# SCH_ECE198-03.net
KiCad netlist of a schematic drawn in EasyEDA
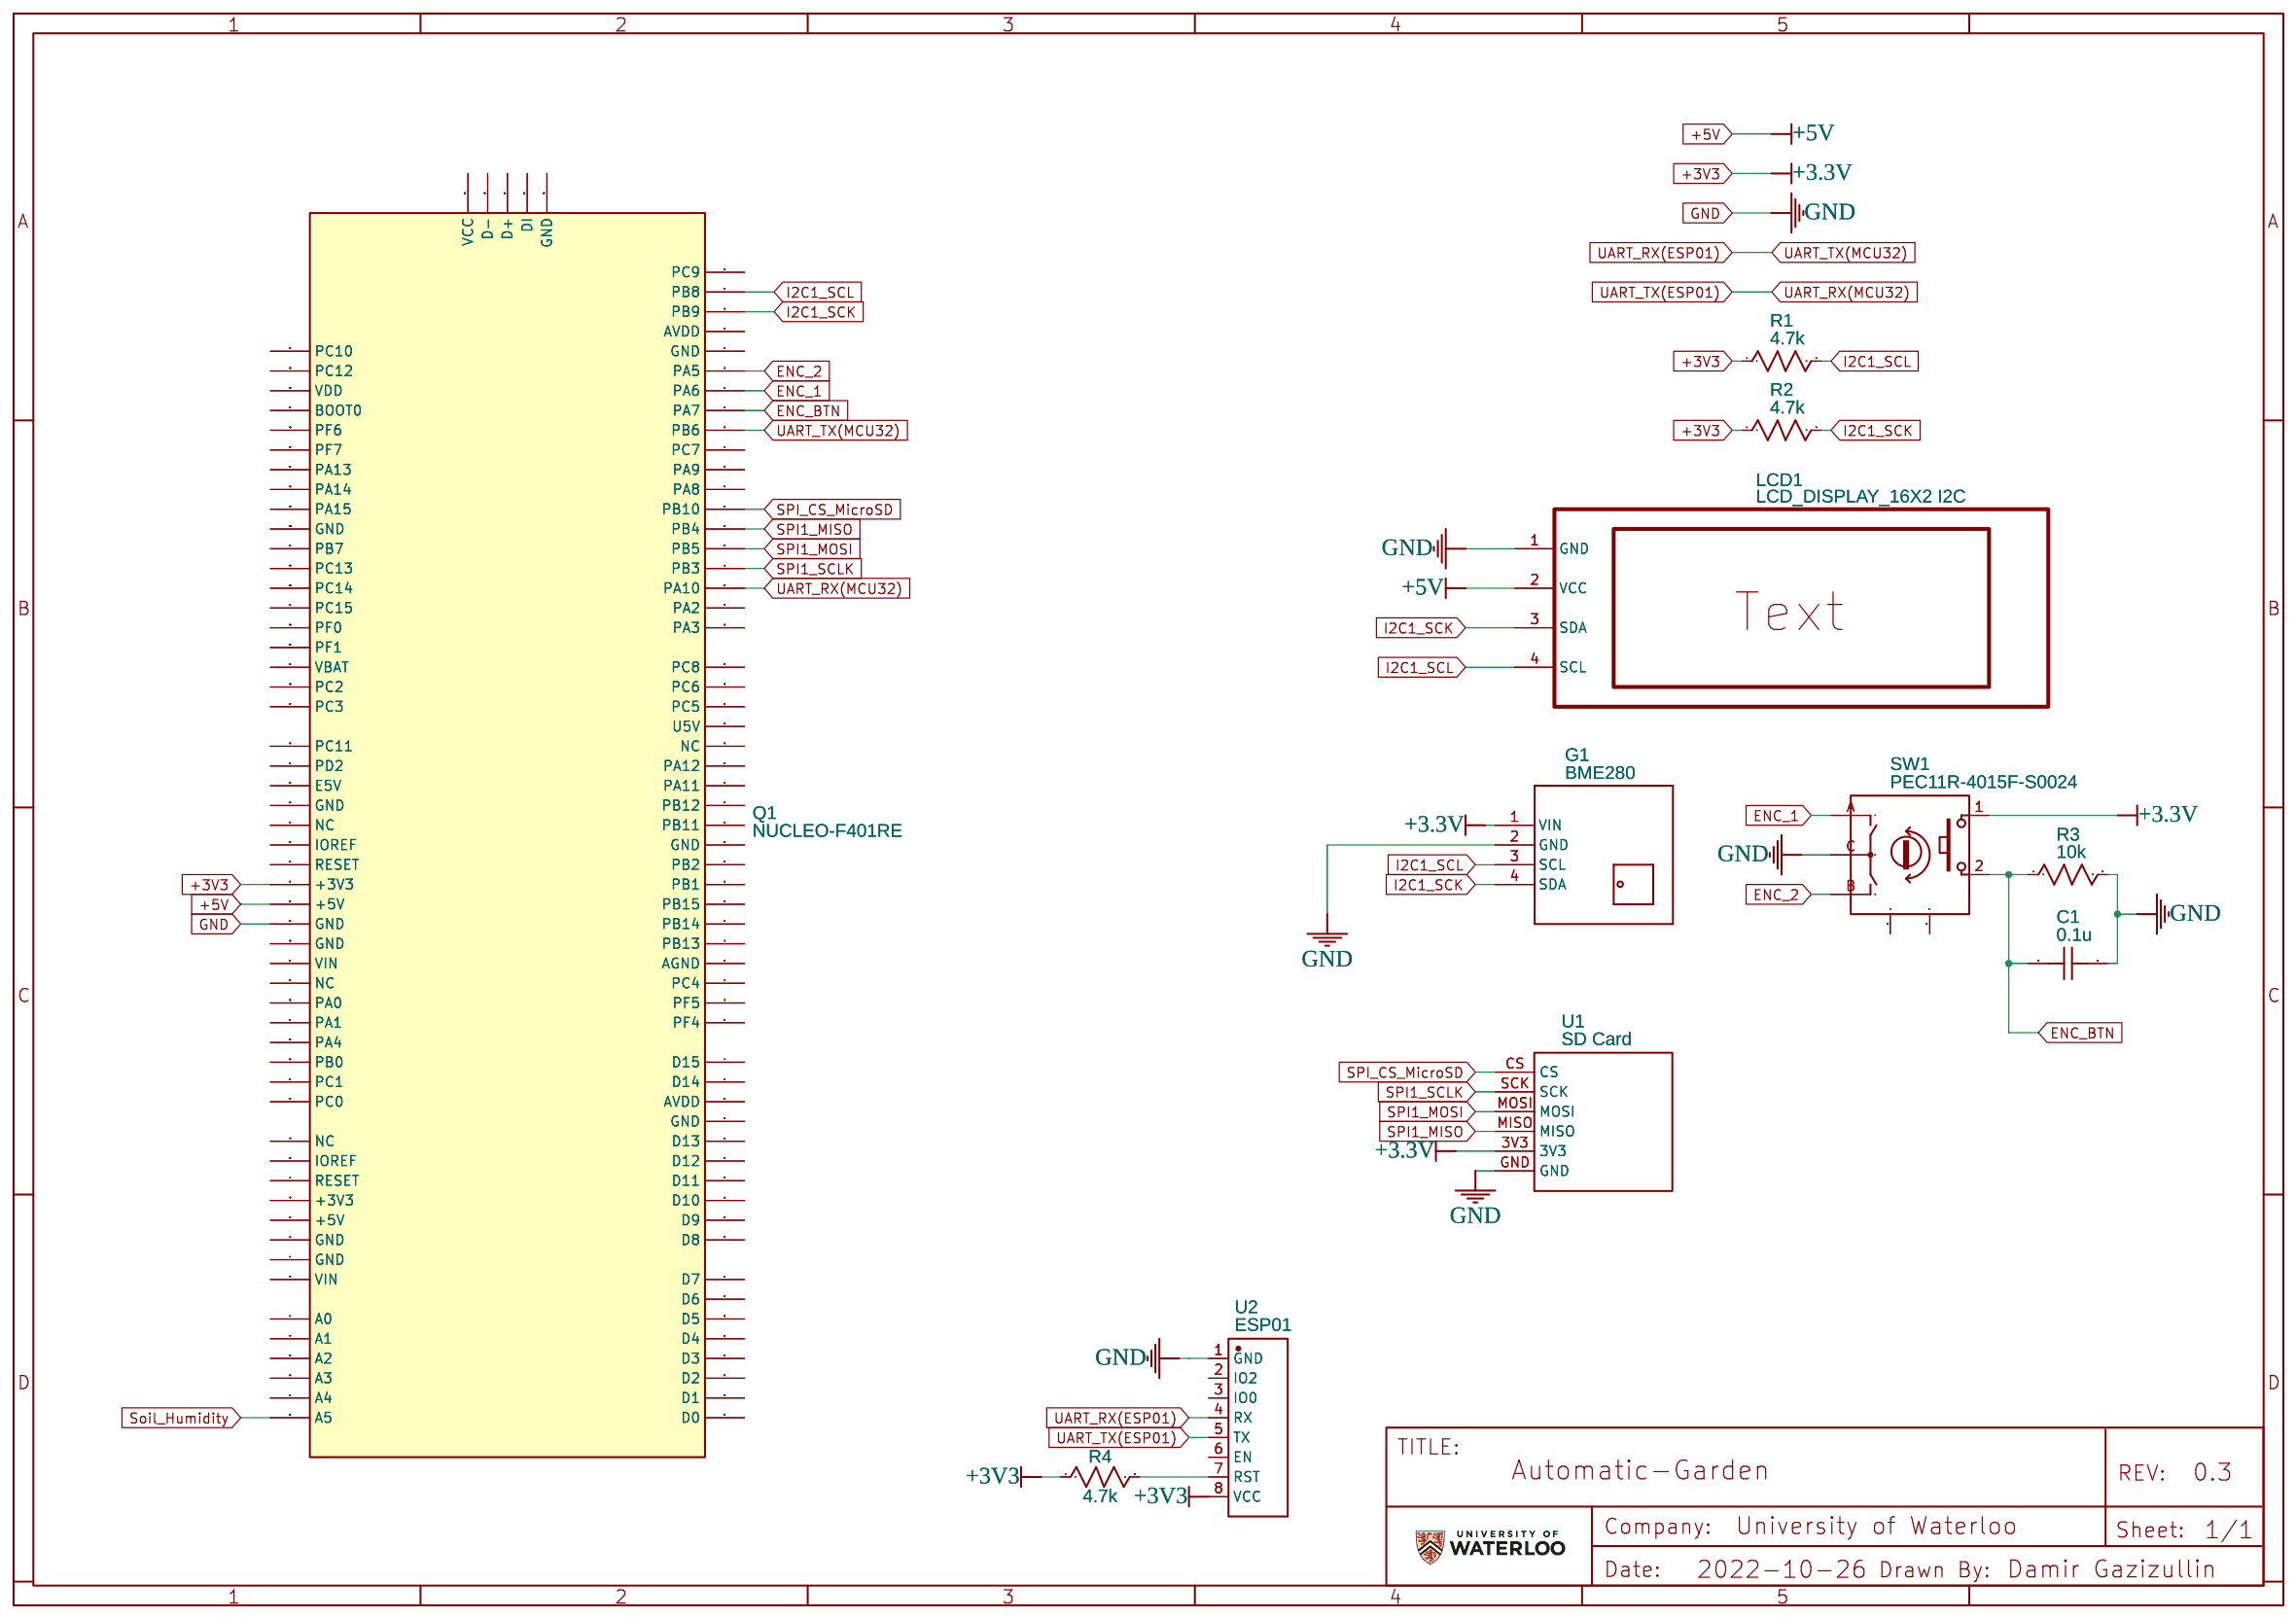
[diagram p0: schematic sheet]

(export (version "E")
  (design (tool "Eeschema 10.0.6"))
  (components
    (comp (ref "C1") (value "0.1u") (libsource (lib "") (part "C_0603_US")))
    (comp (ref "G1") (value "BME280") (libsource (lib "") (part "TEMP-HUM-PRES-BME280")))
    (comp (ref "LCD1") (value "LCD_DISPLAY_16X2 I2C") (libsource (lib "") (part "LCD_DISPLAY_16X2 I2C")))
    (comp (ref "Q1") (value "NUCLEO-F401RE") (libsource (lib "") (part "NUCLEO-F401RE")))
    (comp (ref "R1") (value "4.7k") (libsource (lib "") (part "R_0603_US")))
    (comp (ref "R2") (value "4.7k") (libsource (lib "") (part "R_0603_US")))
    (comp (ref "R3") (value "10k") (libsource (lib "") (part "R_AXIAL-0.5_US")))
    (comp (ref "R4") (value "4.7k") (libsource (lib "") (part "R_AXIAL-0.5_US")))
    (comp (ref "SW1")
      (value "PEC11R-4015F-S0024")
      (fields (field (name "BOM_Supplier Part") "C143789"))
      (libsource (lib "") (part "PEC11R-4015F-S0024"))
    )
    (comp (ref "U1") (value "SD Card") (libsource (lib "") (part "SD Card")))
    (comp (ref "U2") (value "ESP01") (libsource (lib "") (part "ESP01")))
  )
  (nets
    (net (code "1") (name "+3V3") (class "Default")
      (node (ref "G1") (pin "1") (pinfunction "VIN_1") (pintype "bidirectional"))
      (node (ref "Q1") (pin "91") (pinfunction "+3V3_91") (pintype "unspecified"))
      (node (ref "R1") (pin "1") (pinfunction "1_1") (pintype "unspecified"))
      (node (ref "R2") (pin "1") (pinfunction "1_1") (pintype "unspecified"))
      (node (ref "R4") (pin "1") (pinfunction "1_1") (pintype "unspecified"))
      (node (ref "SW1") (pin "1") (pinfunction "1_1") (pintype "unspecified"))
      (node (ref "U1") (pin "3V3") (pinfunction "3V3_3V3") (pintype "unspecified"))
      (node (ref "U2") (pin "8") (pinfunction "VCC_8") (pintype "unspecified"))
    )
    (net (code "2") (name "+5V") (class "Default")
      (node (ref "LCD1") (pin "2") (pinfunction "VCC_2") (pintype "passive"))
      (node (ref "Q1") (pin "90") (pinfunction "+5V_90") (pintype "unspecified"))
    )
    (net (code "3") (name "ENC_1") (class "Default")
      (node (ref "Q1") (pin "14") (pinfunction "PA6_14") (pintype "bidirectional"))
      (node (ref "SW1") (pin "A") (pinfunction "A_A") (pintype "unspecified"))
    )
    (net (code "4") (name "ENC_2") (class "Default")
      (node (ref "Q1") (pin "13") (pinfunction "PA5_13") (pintype "bidirectional"))
      (node (ref "SW1") (pin "B") (pinfunction "B_B") (pintype "unspecified"))
    )
    (net (code "5") (name "ENC_BTN") (class "Default")
      (node (ref "C1") (pin "1") (pinfunction "1_1") (pintype "unspecified"))
      (node (ref "Q1") (pin "15") (pinfunction "PA7_15") (pintype "bidirectional"))
      (node (ref "R3") (pin "1") (pinfunction "1_1") (pintype "unspecified"))
      (node (ref "SW1") (pin "2") (pinfunction "2_2") (pintype "unspecified"))
    )
    (net (code "6") (name "GND") (class "Default")
      (node (ref "C1") (pin "2") (pinfunction "2_2") (pintype "unspecified"))
      (node (ref "G1") (pin "2") (pinfunction "GND_2") (pintype "bidirectional"))
      (node (ref "LCD1") (pin "1") (pinfunction "GND_1") (pintype "passive"))
      (node (ref "Q1") (pin "89") (pinfunction "GND_89") (pintype "unspecified"))
      (node (ref "R3") (pin "2") (pinfunction "2_2") (pintype "unspecified"))
      (node (ref "SW1") (pin "C") (pinfunction "C_C") (pintype "unspecified"))
      (node (ref "U1") (pin "GND") (pinfunction "GND_GND") (pintype "unspecified"))
      (node (ref "U2") (pin "1") (pinfunction "GND_1") (pintype "unspecified"))
    )
    (net (code "7") (name "I2C1_SCK") (class "Default")
      (node (ref "G1") (pin "4") (pinfunction "SDA_4") (pintype "bidirectional"))
      (node (ref "LCD1") (pin "3") (pinfunction "SDA_3") (pintype "passive"))
      (node (ref "Q1") (pin "10") (pinfunction "PB9_10") (pintype "bidirectional"))
      (node (ref "R2") (pin "2") (pinfunction "2_2") (pintype "unspecified"))
    )
    (net (code "8") (name "I2C1_SCL") (class "Default")
      (node (ref "G1") (pin "3") (pinfunction "SCL_3") (pintype "bidirectional"))
      (node (ref "LCD1") (pin "4") (pinfunction "SCL_4") (pintype "passive"))
      (node (ref "Q1") (pin "9") (pinfunction "PB8_9") (pintype "bidirectional"))
      (node (ref "R1") (pin "2") (pinfunction "2_2") (pintype "unspecified"))
    )
    (net (code "9") (name "Net-(U2-RST)") (class "Default")
      (node (ref "R4") (pin "2") (pinfunction "2_2") (pintype "unspecified"))
      (node (ref "U2") (pin "7") (pinfunction "RST_7") (pintype "unspecified"))
    )
    (net (code "10") (name "SPI1_MISO") (class "Default")
      (node (ref "Q1") (pin "21") (pinfunction "PB4_21") (pintype "bidirectional"))
      (node (ref "U1") (pin "MISO") (pinfunction "MISO_MISO") (pintype "unspecified"))
    )
    (net (code "11") (name "SPI1_MOSI") (class "Default")
      (node (ref "Q1") (pin "22") (pinfunction "PB5_22") (pintype "bidirectional"))
      (node (ref "U1") (pin "MOSI") (pinfunction "MOSI_MOSI") (pintype "unspecified"))
    )
    (net (code "12") (name "SPI1_SCLK") (class "Default")
      (node (ref "Q1") (pin "23") (pinfunction "PB3_23") (pintype "bidirectional"))
      (node (ref "U1") (pin "SCK") (pinfunction "SCK_SCK") (pintype "unspecified"))
    )
    (net (code "13") (name "SPI_CS_MicroSD") (class "Default")
      (node (ref "Q1") (pin "20") (pinfunction "PB10_20") (pintype "bidirectional"))
      (node (ref "U1") (pin "CS") (pinfunction "CS_CS") (pintype "unspecified"))
    )
    (net (code "14") (name "Soil_Humidity") (class "Default")
      (node (ref "Q1") (pin "66") (pinfunction "A5_66") (pintype "unspecified"))
    )
    (net (code "15") (name "UART_RX(ESP01)") (class "Default")
      (node (ref "Q1") (pin "16") (pinfunction "PB6_16") (pintype "bidirectional"))
      (node (ref "U2") (pin "4") (pinfunction "RX_4") (pintype "unspecified"))
    )
    (net (code "16") (name "UART_RX(MCU32)") (class "Default")
      (node (ref "Q1") (pin "24") (pinfunction "PA10_24") (pintype "bidirectional"))
      (node (ref "U2") (pin "5") (pinfunction "TX_5") (pintype "unspecified"))
    )
    (net (code "17") (name "unconnected-(Q1-+3V3-Pad76)") (class "Default")
      (node (ref "Q1") (pin "76") (pinfunction "+3V3_76") (pintype "unspecified"))
    )
    (net (code "18") (name "unconnected-(Q1-+5V-Pad75)") (class "Default")
      (node (ref "Q1") (pin "75") (pinfunction "+5V_75") (pintype "unspecified"))
    )
    (net (code "19") (name "unconnected-(Q1-A0-Pad71)") (class "Default")
      (node (ref "Q1") (pin "71") (pinfunction "A0_71") (pintype "unspecified"))
    )
    (net (code "20") (name "unconnected-(Q1-A1-Pad70)") (class "Default")
      (node (ref "Q1") (pin "70") (pinfunction "A1_70") (pintype "unspecified"))
    )
    (net (code "21") (name "unconnected-(Q1-A2-Pad69)") (class "Default")
      (node (ref "Q1") (pin "69") (pinfunction "A2_69") (pintype "unspecified"))
    )
    (net (code "22") (name "unconnected-(Q1-A3-Pad68)") (class "Default")
      (node (ref "Q1") (pin "68") (pinfunction "A3_68") (pintype "unspecified"))
    )
    (net (code "23") (name "unconnected-(Q1-A4-Pad67)") (class "Default")
      (node (ref "Q1") (pin "67") (pinfunction "A4_67") (pintype "unspecified"))
    )
    (net (code "24") (name "unconnected-(Q1-AGND-Pad43)") (class "Default")
      (node (ref "Q1") (pin "43") (pinfunction "AGND_43") (pintype "unspecified"))
    )
    (net (code "25") (name "unconnected-(Q1-AVDD-Pad11)") (class "Default")
      (node (ref "Q1") (pin "11") (pinfunction "AVDD_11") (pintype "bidirectional"))
    )
    (net (code "26") (name "unconnected-(Q1-AVDD-Pad49)") (class "Default")
      (node (ref "Q1") (pin "49") (pinfunction "AVDD_49") (pintype "unspecified"))
    )
    (net (code "27") (name "unconnected-(Q1-BOOT0-Pad114)") (class "Default")
      (node (ref "Q1") (pin "114") (pinfunction "BOOT0_114") (pintype "unspecified"))
    )
    (net (code "28") (name "unconnected-(Q1-D+-Pad118)") (class "Default")
      (node (ref "Q1") (pin "118") (pinfunction "D+_118") (pintype "unspecified"))
    )
    (net (code "29") (name "unconnected-(Q1-D--Pad118)") (class "Default")
      (node (ref "Q1") (pin "118") (pinfunction "D-_118") (pintype "unspecified"))
    )
    (net (code "30") (name "unconnected-(Q1-D0-Pad65)") (class "Default")
      (node (ref "Q1") (pin "65") (pinfunction "D0_65") (pintype "unspecified"))
    )
    (net (code "31") (name "unconnected-(Q1-D1-Pad64)") (class "Default")
      (node (ref "Q1") (pin "64") (pinfunction "D1_64") (pintype "unspecified"))
    )
    (net (code "32") (name "unconnected-(Q1-D2-Pad63)") (class "Default")
      (node (ref "Q1") (pin "63") (pinfunction "D2_63") (pintype "unspecified"))
    )
    (net (code "33") (name "unconnected-(Q1-D3-Pad62)") (class "Default")
      (node (ref "Q1") (pin "62") (pinfunction "D3_62") (pintype "unspecified"))
    )
    (net (code "34") (name "unconnected-(Q1-D4-Pad61)") (class "Default")
      (node (ref "Q1") (pin "61") (pinfunction "D4_61") (pintype "unspecified"))
    )
    (net (code "35") (name "unconnected-(Q1-D5-Pad60)") (class "Default")
      (node (ref "Q1") (pin "60") (pinfunction "D5_60") (pintype "unspecified"))
    )
    (net (code "36") (name "unconnected-(Q1-D6-Pad59)") (class "Default")
      (node (ref "Q1") (pin "59") (pinfunction "D6_59") (pintype "unspecified"))
    )
    (net (code "37") (name "unconnected-(Q1-D7-Pad58)") (class "Default")
      (node (ref "Q1") (pin "58") (pinfunction "D7_58") (pintype "unspecified"))
    )
    (net (code "38") (name "unconnected-(Q1-D8-Pad56)") (class "Default")
      (node (ref "Q1") (pin "56") (pinfunction "D8_56") (pintype "unspecified"))
    )
    (net (code "39") (name "unconnected-(Q1-D9-Pad55)") (class "Default")
      (node (ref "Q1") (pin "55") (pinfunction "D9_55") (pintype "unspecified"))
    )
    (net (code "40") (name "unconnected-(Q1-D10-Pad54)") (class "Default")
      (node (ref "Q1") (pin "54") (pinfunction "D10_54") (pintype "unspecified"))
    )
    (net (code "41") (name "unconnected-(Q1-D11-Pad53)") (class "Default")
      (node (ref "Q1") (pin "53") (pinfunction "D11_53") (pintype "unspecified"))
    )
    (net (code "42") (name "unconnected-(Q1-D12-Pad52)") (class "Default")
      (node (ref "Q1") (pin "52") (pinfunction "D12_52") (pintype "unspecified"))
    )
    (net (code "43") (name "unconnected-(Q1-D13-Pad51)") (class "Default")
      (node (ref "Q1") (pin "51") (pinfunction "D13_51") (pintype "unspecified"))
    )
    (net (code "44") (name "unconnected-(Q1-D14-Pad48)") (class "Default")
      (node (ref "Q1") (pin "48") (pinfunction "D14_48") (pintype "unspecified"))
    )
    (net (code "45") (name "unconnected-(Q1-D15-Pad47)") (class "Default")
      (node (ref "Q1") (pin "47") (pinfunction "D15_47") (pintype "unspecified"))
    )
    (net (code "46") (name "unconnected-(Q1-DI-Pad118)") (class "Default")
      (node (ref "Q1") (pin "118") (pinfunction "DI_118") (pintype "unspecified"))
    )
    (net (code "47") (name "unconnected-(Q1-E5V-Pad96)") (class "Default")
      (node (ref "Q1") (pin "96") (pinfunction "E5V_96") (pintype "unspecified"))
    )
    (net (code "48") (name "unconnected-(Q1-GND-Pad12)") (class "Default")
      (node (ref "Q1") (pin "12") (pinfunction "GND_12") (pintype "bidirectional"))
    )
    (net (code "49") (name "unconnected-(Q1-GND-Pad37)") (class "Default")
      (node (ref "Q1") (pin "37") (pinfunction "GND_37") (pintype "unspecified"))
    )
    (net (code "50") (name "unconnected-(Q1-GND-Pad50)") (class "Default")
      (node (ref "Q1") (pin "50") (pinfunction "GND_50") (pintype "unspecified"))
    )
    (net (code "51") (name "unconnected-(Q1-GND-Pad73)") (class "Default")
      (node (ref "Q1") (pin "73") (pinfunction "GND_73") (pintype "unspecified"))
    )
    (net (code "52") (name "unconnected-(Q1-GND-Pad74)") (class "Default")
      (node (ref "Q1") (pin "74") (pinfunction "GND_74") (pintype "unspecified"))
    )
    (net (code "53") (name "unconnected-(Q1-GND-Pad88)") (class "Default")
      (node (ref "Q1") (pin "88") (pinfunction "GND_88") (pintype "unspecified"))
    )
    (net (code "54") (name "unconnected-(Q1-GND-Pad95)") (class "Default")
      (node (ref "Q1") (pin "95") (pinfunction "GND_95") (pintype "unspecified"))
    )
    (net (code "55") (name "unconnected-(Q1-GND-Pad108)") (class "Default")
      (node (ref "Q1") (pin "108") (pinfunction "GND_108") (pintype "unspecified"))
    )
    (net (code "56") (name "unconnected-(Q1-GND-Pad118)") (class "Default")
      (node (ref "Q1") (pin "118") (pinfunction "GND_118") (pintype "unspecified"))
    )
    (net (code "57") (name "unconnected-(Q1-IOREF-Pad78)") (class "Default")
      (node (ref "Q1") (pin "78") (pinfunction "IOREF_78") (pintype "unspecified"))
    )
    (net (code "58") (name "unconnected-(Q1-IOREF-Pad93)") (class "Default")
      (node (ref "Q1") (pin "93") (pinfunction "IOREF_93") (pintype "unspecified"))
    )
    (net (code "59") (name "unconnected-(Q1-NC-Pad32)") (class "Default")
      (node (ref "Q1") (pin "32") (pinfunction "NC_32") (pintype "bidirectional"))
    )
    (net (code "60") (name "unconnected-(Q1-NC-Pad79)") (class "Default")
      (node (ref "Q1") (pin "79") (pinfunction "NC_79") (pintype "unspecified"))
    )
    (net (code "61") (name "unconnected-(Q1-NC-Pad86)") (class "Default")
      (node (ref "Q1") (pin "86") (pinfunction "NC_86") (pintype "unspecified"))
    )
    (net (code "62") (name "unconnected-(Q1-NC-Pad94)") (class "Default")
      (node (ref "Q1") (pin "94") (pinfunction "NC_94") (pintype "unspecified"))
    )
    (net (code "63") (name "unconnected-(Q1-PA0-Pad85)") (class "Default")
      (node (ref "Q1") (pin "85") (pinfunction "PA0_85") (pintype "unspecified"))
    )
    (net (code "64") (name "unconnected-(Q1-PA1-Pad84)") (class "Default")
      (node (ref "Q1") (pin "84") (pinfunction "PA1_84") (pintype "unspecified"))
    )
    (net (code "65") (name "unconnected-(Q1-PA2-Pad25)") (class "Default")
      (node (ref "Q1") (pin "25") (pinfunction "PA2_25") (pintype "bidirectional"))
    )
    (net (code "66") (name "unconnected-(Q1-PA3-Pad26)") (class "Default")
      (node (ref "Q1") (pin "26") (pinfunction "PA3_26") (pintype "bidirectional"))
    )
    (net (code "67") (name "unconnected-(Q1-PA4-Pad83)") (class "Default")
      (node (ref "Q1") (pin "83") (pinfunction "PA4_83") (pintype "unspecified"))
    )
    (net (code "68") (name "unconnected-(Q1-PA8-Pad19)") (class "Default")
      (node (ref "Q1") (pin "19") (pinfunction "PA8_19") (pintype "bidirectional"))
    )
    (net (code "69") (name "unconnected-(Q1-PA9-Pad18)") (class "Default")
      (node (ref "Q1") (pin "18") (pinfunction "PA9_18") (pintype "bidirectional"))
    )
    (net (code "70") (name "unconnected-(Q1-PA11-Pad34)") (class "Default")
      (node (ref "Q1") (pin "34") (pinfunction "PA11_34") (pintype "bidirectional"))
    )
    (net (code "71") (name "unconnected-(Q1-PA12-Pad33)") (class "Default")
      (node (ref "Q1") (pin "33") (pinfunction "PA12_33") (pintype "bidirectional"))
    )
    (net (code "72") (name "unconnected-(Q1-PA13-Pad111)") (class "Default")
      (node (ref "Q1") (pin "111") (pinfunction "PA13_111") (pintype "unspecified"))
    )
    (net (code "73") (name "unconnected-(Q1-PA14-Pad110)") (class "Default")
      (node (ref "Q1") (pin "110") (pinfunction "PA14_110") (pintype "unspecified"))
    )
    (net (code "74") (name "unconnected-(Q1-PA15-Pad109)") (class "Default")
      (node (ref "Q1") (pin "109") (pinfunction "PA15_109") (pintype "unspecified"))
    )
    (net (code "75") (name "unconnected-(Q1-PB0-Pad82)") (class "Default")
      (node (ref "Q1") (pin "82") (pinfunction "PB0_82") (pintype "unspecified"))
    )
    (net (code "76") (name "unconnected-(Q1-PB1-Pad39)") (class "Default")
      (node (ref "Q1") (pin "39") (pinfunction "PB1_39") (pintype "unspecified"))
    )
    (net (code "77") (name "unconnected-(Q1-PB2-Pad38)") (class "Default")
      (node (ref "Q1") (pin "38") (pinfunction "PB2_38") (pintype "unspecified"))
    )
    (net (code "78") (name "unconnected-(Q1-PB7-Pad107)") (class "Default")
      (node (ref "Q1") (pin "107") (pinfunction "PB7_107") (pintype "unspecified"))
    )
    (net (code "79") (name "unconnected-(Q1-PB11-Pad36)") (class "Default")
      (node (ref "Q1") (pin "36") (pinfunction "PB11_36") (pintype "unspecified"))
    )
    (net (code "80") (name "unconnected-(Q1-PB12-Pad35)") (class "Default")
      (node (ref "Q1") (pin "35") (pinfunction "PB12_35") (pintype "unspecified"))
    )
    (net (code "81") (name "unconnected-(Q1-PB13-Pad42)") (class "Default")
      (node (ref "Q1") (pin "42") (pinfunction "PB13_42") (pintype "unspecified"))
    )
    (net (code "82") (name "unconnected-(Q1-PB14-Pad41)") (class "Default")
      (node (ref "Q1") (pin "41") (pinfunction "PB14_41") (pintype "unspecified"))
    )
    (net (code "83") (name "unconnected-(Q1-PB15-Pad40)") (class "Default")
      (node (ref "Q1") (pin "40") (pinfunction "PB15_40") (pintype "unspecified"))
    )
    (net (code "84") (name "unconnected-(Q1-PC0-Pad80)") (class "Default")
      (node (ref "Q1") (pin "80") (pinfunction "PC0_80") (pintype "unspecified"))
    )
    (net (code "85") (name "unconnected-(Q1-PC1-Pad81)") (class "Default")
      (node (ref "Q1") (pin "81") (pinfunction "PC1_81") (pintype "unspecified"))
    )
    (net (code "86") (name "unconnected-(Q1-PC2-Pad100)") (class "Default")
      (node (ref "Q1") (pin "100") (pinfunction "PC2_100") (pintype "unspecified"))
    )
    (net (code "87") (name "unconnected-(Q1-PC3-Pad99)") (class "Default")
      (node (ref "Q1") (pin "99") (pinfunction "PC3_99") (pintype "unspecified"))
    )
    (net (code "88") (name "unconnected-(Q1-PC4-Pad44)") (class "Default")
      (node (ref "Q1") (pin "44") (pinfunction "PC4_44") (pintype "unspecified"))
    )
    (net (code "89") (name "unconnected-(Q1-PC5-Pad30)") (class "Default")
      (node (ref "Q1") (pin "30") (pinfunction "PC5_30") (pintype "bidirectional"))
    )
    (net (code "90") (name "unconnected-(Q1-PC6-Pad29)") (class "Default")
      (node (ref "Q1") (pin "29") (pinfunction "PC6_29") (pintype "bidirectional"))
    )
    (net (code "91") (name "unconnected-(Q1-PC7-Pad17)") (class "Default")
      (node (ref "Q1") (pin "17") (pinfunction "PC7_17") (pintype "bidirectional"))
    )
    (net (code "92") (name "unconnected-(Q1-PC8-Pad28)") (class "Default")
      (node (ref "Q1") (pin "28") (pinfunction "PC8_28") (pintype "bidirectional"))
    )
    (net (code "93") (name "unconnected-(Q1-PC9-Pad8)") (class "Default")
      (node (ref "Q1") (pin "8") (pinfunction "PC9_8") (pintype "bidirectional"))
    )
    (net (code "94") (name "unconnected-(Q1-PC10-Pad117)") (class "Default")
      (node (ref "Q1") (pin "117") (pinfunction "PC10_117") (pintype "unspecified"))
    )
    (net (code "95") (name "unconnected-(Q1-PC11-Pad98)") (class "Default")
      (node (ref "Q1") (pin "98") (pinfunction "PC11_98") (pintype "unspecified"))
    )
    (net (code "96") (name "unconnected-(Q1-PC12-Pad116)") (class "Default")
      (node (ref "Q1") (pin "116") (pinfunction "PC12_116") (pintype "unspecified"))
    )
    (net (code "97") (name "unconnected-(Q1-PC13-Pad106)") (class "Default")
      (node (ref "Q1") (pin "106") (pinfunction "PC13_106") (pintype "unspecified"))
    )
    (net (code "98") (name "unconnected-(Q1-PC14-Pad105)") (class "Default")
      (node (ref "Q1") (pin "105") (pinfunction "PC14_105") (pintype "unspecified"))
    )
    (net (code "99") (name "unconnected-(Q1-PC15-Pad104)") (class "Default")
      (node (ref "Q1") (pin "104") (pinfunction "PC15_104") (pintype "unspecified"))
    )
    (net (code "100") (name "unconnected-(Q1-PD2-Pad97)") (class "Default")
      (node (ref "Q1") (pin "97") (pinfunction "PD2_97") (pintype "unspecified"))
    )
    (net (code "101") (name "unconnected-(Q1-PF0-Pad103)") (class "Default")
      (node (ref "Q1") (pin "103") (pinfunction "PF0_103") (pintype "unspecified"))
    )
    (net (code "102") (name "unconnected-(Q1-PF1-Pad102)") (class "Default")
      (node (ref "Q1") (pin "102") (pinfunction "PF1_102") (pintype "unspecified"))
    )
    (net (code "103") (name "unconnected-(Q1-PF4-Pad46)") (class "Default")
      (node (ref "Q1") (pin "46") (pinfunction "PF4_46") (pintype "unspecified"))
    )
    (net (code "104") (name "unconnected-(Q1-PF5-Pad45)") (class "Default")
      (node (ref "Q1") (pin "45") (pinfunction "PF5_45") (pintype "unspecified"))
    )
    (net (code "105") (name "unconnected-(Q1-PF6-Pad113)") (class "Default")
      (node (ref "Q1") (pin "113") (pinfunction "PF6_113") (pintype "unspecified"))
    )
    (net (code "106") (name "unconnected-(Q1-PF7-Pad112)") (class "Default")
      (node (ref "Q1") (pin "112") (pinfunction "PF7_112") (pintype "unspecified"))
    )
    (net (code "107") (name "unconnected-(Q1-RESET-Pad77)") (class "Default")
      (node (ref "Q1") (pin "77") (pinfunction "RESET_77") (pintype "unspecified"))
    )
    (net (code "108") (name "unconnected-(Q1-RESET-Pad92)") (class "Default")
      (node (ref "Q1") (pin "92") (pinfunction "RESET_92") (pintype "unspecified"))
    )
    (net (code "109") (name "unconnected-(Q1-U5V-Pad31)") (class "Default")
      (node (ref "Q1") (pin "31") (pinfunction "U5V_31") (pintype "bidirectional"))
    )
    (net (code "110") (name "unconnected-(Q1-VBAT-Pad101)") (class "Default")
      (node (ref "Q1") (pin "101") (pinfunction "VBAT_101") (pintype "unspecified"))
    )
    (net (code "111") (name "unconnected-(Q1-VCC-Pad118)") (class "Default")
      (node (ref "Q1") (pin "118") (pinfunction "VCC_118") (pintype "unspecified"))
    )
    (net (code "112") (name "unconnected-(Q1-VDD-Pad115)") (class "Default")
      (node (ref "Q1") (pin "115") (pinfunction "VDD_115") (pintype "unspecified"))
    )
    (net (code "113") (name "unconnected-(Q1-VIN-Pad72)") (class "Default")
      (node (ref "Q1") (pin "72") (pinfunction "VIN_72") (pintype "unspecified"))
    )
    (net (code "114") (name "unconnected-(Q1-VIN-Pad87)") (class "Default")
      (node (ref "Q1") (pin "87") (pinfunction "VIN_87") (pintype "unspecified"))
    )
    (net (code "115") (name "unconnected-(SW1-PadMT1)") (class "Default")
      (node (ref "SW1") (pin "MT1") (pinfunction "MT1_MT1") (pintype "unspecified"))
    )
    (net (code "116") (name "unconnected-(SW1-PadMT2)") (class "Default")
      (node (ref "SW1") (pin "MT2") (pinfunction "MT2_MT2") (pintype "unspecified"))
    )
    (net (code "117") (name "unconnected-(U2-EN-Pad6)") (class "Default")
      (node (ref "U2") (pin "6") (pinfunction "EN_6") (pintype "unspecified"))
    )
    (net (code "118") (name "unconnected-(U2-IO0-Pad3)") (class "Default")
      (node (ref "U2") (pin "3") (pinfunction "IO0_3") (pintype "unspecified"))
    )
    (net (code "119") (name "unconnected-(U2-IO2-Pad2)") (class "Default")
      (node (ref "U2") (pin "2") (pinfunction "IO2_2") (pintype "unspecified"))
    )
  )
)
